# 02_Mobile_Power.net
KiCad netlist of a schematic drawn in Altium Designer
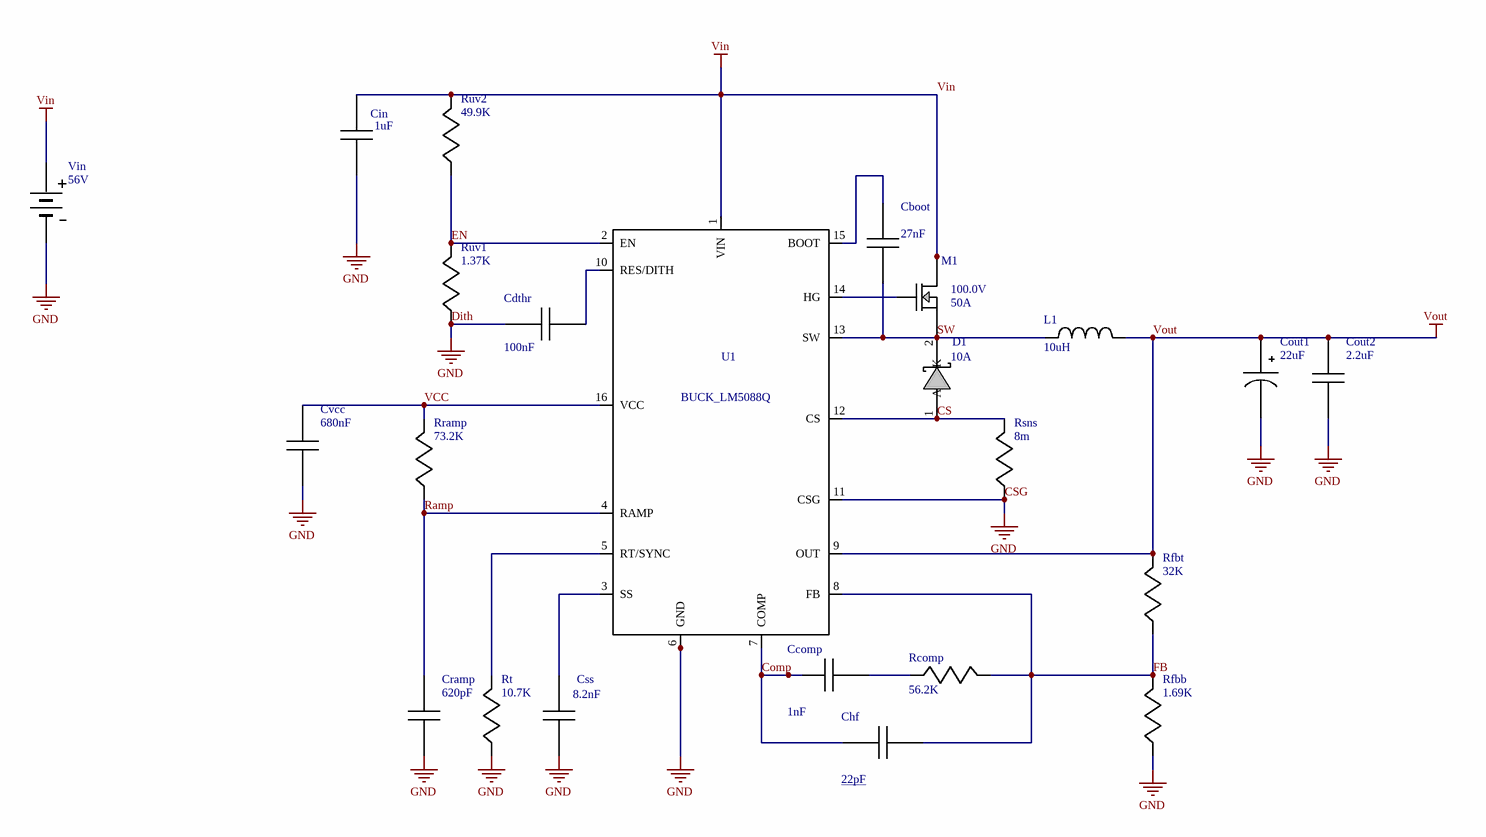
[diagram p0: 02 Mobile Power.SchDoc]

(export (version "E")
  (design (tool "Eeschema 10.0.6"))
  (components
    (comp (ref "Cboot")
      (value "CAP_27nF")
      (footprint "1812")
      (description "Imported")
      (fields
        (field (name "MANUFACTURER_PART_NUMBER") "C1812C273J5GACTU")
        (field (name "MANUFACTURER") "KEMET")
        (field (name "CAPACITANCE") "27nF")
      )
      (libsource (lib "ECE453_PWR") (part "CAP_27nF"))
    )
    (comp (ref "Ccomp")
      (value "1nF")
      (footprint "0805")
      (description "Imported")
      (fields
        (field (name "MANUFACTURER_PART_NUMBER") "C0805C102K5GACTU")
        (field (name "MANUFACTURER") "KEMET")
        (field (name "CAPACITANCE") "1nF")
      )
      (libsource (lib "ECE453_PWR") (part "CAP_1nF"))
    )
    (comp (ref "Cdthr")
      (value "100nF")
      (footprint "0805")
      (description "Imported")
      (fields
        (field (name "MANUFACTURER_PART_NUMBER") "08053C104JAZ2A")
        (field (name "MANUFACTURER") "AVX Corporation")
      )
      (libsource (lib "ECE453_PWR") (part "CAP_100nF"))
    )
    (comp (ref "Chf")
      (value "CAP_22pF")
      (footprint "0805")
      (description "Imported")
      (fields
        (field (name "MANUFACTURER_PART_NUMBER") "C0805C220K3GACTU")
        (field (name "MANUFACTURER") "KEMET")
        (field (name "CAPACITANCE") "22pF")
      )
      (libsource (lib "ECE453_PWR") (part "CAP_22pF"))
    )
    (comp (ref "Cin")
      (value "1uF")
      (footprint "1206_180")
      (description "Imported")
      (fields
        (field (name "MANUFACTURER_PART_NUMBER") "C3216X7R2A105K160AA")
        (field (name "MANUFACTURER") "TDK Corporation")
        (field (name "CAPACITANCE") "1uF")
      )
      (libsource (lib "ECE453_PWR") (part "CAP_1uF"))
    )
    (comp (ref "Cout1")
      (value "22uF")
      (footprint "CAPSMT_62_F61")
      (description "Imported")
      (fields
        (field (name "MANUFACTURER_PART_NUMBER") "35SVPF22M")
        (field (name "MANUFACTURER") "Panasonic Electronic Components")
      )
      (libsource (lib "ECE453_PWR") (part "PCAP_22uF"))
    )
    (comp (ref "Cout2")
      (value "2.2uF")
      (footprint "0805")
      (description "Imported")
      (fields
        (field (name "MANUFACTURER_PART_NUMBER") "C2012X7R1H225K125AC")
        (field (name "MANUFACTURER") "TDK Corporation")
      )
      (libsource (lib "ECE453_PWR") (part "CAP_2.2uF"))
    )
    (comp (ref "Cramp")
      (value "620pF")
      (footprint "0805")
      (description "Imported")
      (fields
        (field (name "MANUFACTURER_PART_NUMBER") "CL21C621JBCNNNC")
        (field (name "MANUFACTURER") "Samsung Electro-Mechanics")
      )
      (libsource (lib "ECE453_PWR") (part "CAP_620pF"))
    )
    (comp (ref "Css")
      (value "8.2nF")
      (footprint "0805")
      (description "Imported")
      (fields
        (field (name "MANUFACTURER") "Murata Electronics North America")
        (field (name "MANUFACTURER PART NUMBER") "GRM2195C1H822JA01D")
        (field (name "CAPACITANCE") "8.2nF")
      )
      (libsource (lib "ECE453_PWR") (part "CAP_8.2nF"))
    )
    (comp (ref "Cvcc")
      (value "680nF")
      (footprint "1206")
      (description "Imported")
      (fields
        (field (name "MANUFACTURER_PART_NUMBER") "ECPU1C684MA5")
        (field (name "MANUFACTURER") "Panasonic Electronic Components")
      )
      (libsource (lib "ECE453_PWR") (part "CAP_680nF"))
    )
    (comp (ref "D1")
      (value "DIO_SCHOTT_1655-1099-ND")
      (footprint "DPAK")
      (description "Imported")
      (fields
        (field (name "MANUFACTURER") "SMC Diode Solutions")
        (field (name "MANUFACTURER PART NUMBER") "MBRF10200")
        (field (name "CURRENT - AVERAGE RECTIFIED (IO)") "10A")
      )
      (libsource (lib "ECE453_PWR") (part "DIO_SCHOTT_1655-1099-ND"))
    )
    (comp (ref "L1")
      (value "10uH")
      (footprint "SER2915")
      (description "Imported")
      (fields
        (field (name "MANUFACTURER_PART_NUMBER") "SER2915L-103KL")
        (field (name "MANUFACTURER") "COILCRAFT")
      )
      (libsource (lib "ECE453_PWR") (part "IND_10uH"))
    )
    (comp (ref "M1")
      (value "MOS_CSD19534Q5A")
      (footprint "TRANS_NexFET_Q5A")
      (description "Imported")
      (fields
        (field (name "VDSMAX") "100.0V")
        (field (name "MANUFACTURER_PART_NUMBER") "CSD19534Q5A")
        (field (name "MANUFACTURER") "Texas Instruments")
        (field (name "CURRENT - CONTINUOUS DRAIN (ID) @ 25°C") "50A")
      )
      (libsource (lib "ECE453_PWR") (part "MOS_CSD19534Q5A"))
    )
    (comp (ref "Rcomp")
      (value "56.2K")
      (footprint "0805")
      (description "Imported")
      (fields
        (field (name "MANUFACTURER_PART_NUMBER") "ERJ-6ENF5622V")
        (field (name "MANUFACTURER") "Panasonic Electronic Components")
      )
      (libsource (lib "ECE453_PWR") (part "RES_56.2K"))
    )
    (comp (ref "Rfbb")
      (value "1.69K")
      (footprint "0805")
      (description "Imported")
      (fields
        (field (name "MANUFACTURER_PART_NUMBER") "ERJ-6ENF1691V")
        (field (name "MANUFACTURER") "Panasonic Electronic Components")
      )
      (libsource (lib "ECE453_PWR") (part "RES_1.69K"))
    )
    (comp (ref "Rfbt")
      (value "32K")
      (footprint "0805")
      (description "Imported")
      (fields
        (field (name "MANUFACTURER") "Vishay Dale")
        (field (name "MANUFACTURER PART NUMBER") "TNPW040232K0BEED")
      )
      (libsource (lib "ECE453_PWR") (part "RES_32K"))
    )
    (comp (ref "Rramp")
      (value "73.2K")
      (footprint "0805")
      (description "Imported")
      (fields
        (field (name "MANUFACTURER_PART_NUMBER") "ERJ-6ENF7322V")
        (field (name "MANUFACTURER") "Panasonic Electronic Components")
      )
      (libsource (lib "ECE453_PWR") (part "RES_73.2K"))
    )
    (comp (ref "Rsns")
      (value "8m")
      (footprint "0612")
      (description "Imported")
      (fields
        (field (name "MANUFACTURER_PART_NUMBER") "PRL1632-R008-F-T1")
        (field (name "MANUFACTURER") "Susumu")
      )
      (libsource (lib "ECE453_PWR") (part "RES_8m"))
    )
    (comp (ref "Rt")
      (value "10.7K")
      (footprint "0805")
      (description "Imported")
      (fields
        (field (name "MANUFACTURER_PART_NUMBER") "ERJ-6ENF1072V")
        (field (name "MANUFACTURER") "Panasonic Electronic Components")
      )
      (libsource (lib "ECE453_PWR") (part "RES_10.7K"))
    )
    (comp (ref "Ruv1")
      (value "1.37K")
      (footprint "0805")
      (description "Imported")
      (fields
        (field (name "MANUFACTURER_PART_NUMBER") "CRCW08051K37FKEA")
        (field (name "MANUFACTURER") "Vishay Dale")
      )
      (libsource (lib "ECE453_PWR") (part "RES_1.37K"))
    )
    (comp (ref "Ruv2")
      (value "49.9K")
      (footprint "0805")
      (description "Imported")
      (fields
        (field (name "MANUFACTURER_PART_NUMBER") "ERJ-6ENF4992V")
        (field (name "MANUFACTURER") "Panasonic Electronic Components")
      )
      (libsource (lib "ECE453_PWR") (part "RES_49.9K"))
    )
    (comp (ref "U1")
      (value "BUCK_LM5088Q")
      (footprint "MXA16A")
      (description "Imported")
      (fields
        (field (name "MANUFACTURER_PART_NUMBER") "LM5088MHX-2/NOPB")
        (field (name "MANUFACTURER") "Texas Instruments")
      )
      (libsource (lib "ECE453_PWR") (part "BUCK_LM5088QMHX-1/NOP"))
    )
    (comp (ref "Vin")
      (value "56V")
      (description "Imported")
      (fields (field (name "MANUFACTURER_PART_NUMBER") "WB_BATTERY"))
      (libsource (lib "ECE453_PWR") (part "WB_BATTERY"))
    )
  )
  (nets
    (net (code "1") (name "/CS") (class "Default")
      (node (ref "D1") (pin "1") (pinfunction "A_1") (pintype "passive"))
      (node (ref "D1") (pin "3") (pinfunction "A_3") (pintype "passive"))
      (node (ref "Rsns") (pin "1") (pinfunction "1_1") (pintype "passive"))
      (node (ref "U1") (pin "12") (pinfunction "CS_12") (pintype "passive"))
    )
    (net (code "2") (name "/Comp") (class "Default")
      (node (ref "Ccomp") (pin "2") (pinfunction "2_2") (pintype "passive"))
      (node (ref "Chf") (pin "2") (pinfunction "2_2") (pintype "passive"))
      (node (ref "U1") (pin "7") (pinfunction "COMP_7") (pintype "passive"))
    )
    (net (code "3") (name "/EN") (class "Default")
      (node (ref "Ruv1") (pin "1") (pinfunction "1_1") (pintype "passive"))
      (node (ref "Ruv2") (pin "2") (pinfunction "2_2") (pintype "passive"))
      (node (ref "U1") (pin "2") (pinfunction "EN_2") (pintype "passive"))
    )
    (net (code "4") (name "/FB") (class "Default")
      (node (ref "Chf") (pin "1") (pinfunction "1_1") (pintype "passive"))
      (node (ref "Rcomp") (pin "1") (pinfunction "1_1") (pintype "passive"))
      (node (ref "Rfbb") (pin "1") (pinfunction "1_1") (pintype "passive"))
      (node (ref "Rfbt") (pin "2") (pinfunction "2_2") (pintype "passive"))
      (node (ref "U1") (pin "8") (pinfunction "FB_8") (pintype "passive"))
    )
    (net (code "5") (name "/Ramp") (class "Default")
      (node (ref "Cramp") (pin "1") (pinfunction "1_1") (pintype "passive"))
      (node (ref "Rramp") (pin "2") (pinfunction "2_2") (pintype "passive"))
      (node (ref "U1") (pin "4") (pinfunction "RAMP_4") (pintype "passive"))
    )
    (net (code "6") (name "/SW") (class "Default")
      (node (ref "Cboot") (pin "2") (pinfunction "2_2") (pintype "passive"))
      (node (ref "D1") (pin "2") (pinfunction "K_2") (pintype "passive"))
      (node (ref "L1") (pin "1") (pinfunction "1_1") (pintype "passive"))
      (node (ref "M1") (pin "1") (pinfunction "Source_1") (pintype "passive"))
      (node (ref "M1") (pin "2") (pinfunction "Source_2") (pintype "passive"))
      (node (ref "M1") (pin "3") (pinfunction "Source_3") (pintype "passive"))
      (node (ref "U1") (pin "13") (pinfunction "SW_13") (pintype "passive"))
    )
    (net (code "7") (name "/VCC") (class "Default")
      (node (ref "Cvcc") (pin "1") (pinfunction "1_1") (pintype "passive"))
      (node (ref "Rramp") (pin "1") (pinfunction "1_1") (pintype "passive"))
      (node (ref "U1") (pin "16") (pinfunction "VCC_16") (pintype "passive"))
    )
    (net (code "8") (name "GND") (class "Default")
      (node (ref "Cdthr") (pin "2") (pinfunction "2_2") (pintype "passive"))
      (node (ref "Cin") (pin "2") (pinfunction "2_2") (pintype "passive"))
      (node (ref "Cout1") (pin "2") (pinfunction "-_2") (pintype "passive"))
      (node (ref "Cout2") (pin "2") (pinfunction "2_2") (pintype "passive"))
      (node (ref "Cramp") (pin "2") (pinfunction "2_2") (pintype "passive"))
      (node (ref "Css") (pin "2") (pinfunction "2_2") (pintype "passive"))
      (node (ref "Cvcc") (pin "2") (pinfunction "2_2") (pintype "passive"))
      (node (ref "Rfbb") (pin "2") (pinfunction "2_2") (pintype "passive"))
      (node (ref "Rsns") (pin "2") (pinfunction "2_2") (pintype "passive"))
      (node (ref "Rt") (pin "2") (pinfunction "2_2") (pintype "passive"))
      (node (ref "Ruv1") (pin "2") (pinfunction "2_2") (pintype "passive"))
      (node (ref "U1") (pin "11") (pinfunction "CSG_11") (pintype "passive"))
      (node (ref "U1") (pin "17") (pinfunction "EP_17") (pintype "passive"))
      (node (ref "U1") (pin "6") (pinfunction "GND_6") (pintype "power_in"))
      (node (ref "Vin") (pin "2") (pinfunction "-_2") (pintype "passive"))
    )
    (net (code "9") (name "Net-(Ccomp-Pad1)") (class "Default")
      (node (ref "Ccomp") (pin "1") (pinfunction "1_1") (pintype "passive"))
      (node (ref "Rcomp") (pin "2") (pinfunction "2_2") (pintype "passive"))
    )
    (net (code "10") (name "Net-(M1-Gate)") (class "Default")
      (node (ref "M1") (pin "4") (pinfunction "Gate_4") (pintype "passive"))
      (node (ref "U1") (pin "14") (pinfunction "HG_14") (pintype "passive"))
    )
    (net (code "11") (name "Net-(U1-BOOT)") (class "Default")
      (node (ref "Cboot") (pin "1") (pinfunction "1_1") (pintype "passive"))
      (node (ref "U1") (pin "15") (pinfunction "BOOT_15") (pintype "passive"))
    )
    (net (code "12") (name "Net-(U1-RES{slash}DITH)") (class "Default")
      (node (ref "Cdthr") (pin "1") (pinfunction "1_1") (pintype "passive"))
      (node (ref "U1") (pin "10") (pinfunction "RES/DITH_10") (pintype "passive"))
    )
    (net (code "13") (name "Net-(U1-RT{slash}SYNC)") (class "Default")
      (node (ref "Rt") (pin "1") (pinfunction "1_1") (pintype "passive"))
      (node (ref "U1") (pin "5") (pinfunction "RT/SYNC_5") (pintype "passive"))
    )
    (net (code "14") (name "Net-(U1-SS)") (class "Default")
      (node (ref "Css") (pin "1") (pinfunction "1_1") (pintype "passive"))
      (node (ref "U1") (pin "3") (pinfunction "SS_3") (pintype "passive"))
    )
    (net (code "15") (name "Vin") (class "Default")
      (node (ref "Cin") (pin "1") (pinfunction "1_1") (pintype "passive"))
      (node (ref "M1") (pin "5") (pinfunction "Drain_5") (pintype "passive"))
      (node (ref "M1") (pin "6") (pinfunction "Drain_6") (pintype "passive"))
      (node (ref "M1") (pin "7") (pinfunction "Drain_7") (pintype "passive"))
      (node (ref "M1") (pin "8") (pinfunction "Drain_8") (pintype "passive"))
      (node (ref "M1") (pin "9") (pinfunction "Drain_9") (pintype "passive"))
      (node (ref "Ruv2") (pin "1") (pinfunction "1_1") (pintype "passive"))
      (node (ref "U1") (pin "1") (pinfunction "VIN_1") (pintype "power_in"))
      (node (ref "Vin") (pin "1") (pinfunction "+_1") (pintype "passive"))
    )
    (net (code "16") (name "Vout") (class "Default")
      (node (ref "Cout1") (pin "1") (pinfunction "+_1") (pintype "passive"))
      (node (ref "Cout2") (pin "1") (pinfunction "1_1") (pintype "passive"))
      (node (ref "L1") (pin "2") (pinfunction "2_2") (pintype "passive"))
      (node (ref "Rfbt") (pin "1") (pinfunction "1_1") (pintype "passive"))
      (node (ref "U1") (pin "9") (pinfunction "OUT_9") (pintype "passive"))
    )
  )
)
